# ProyectoFinal.net
KiCad netlist of a schematic drawn in EAGLE
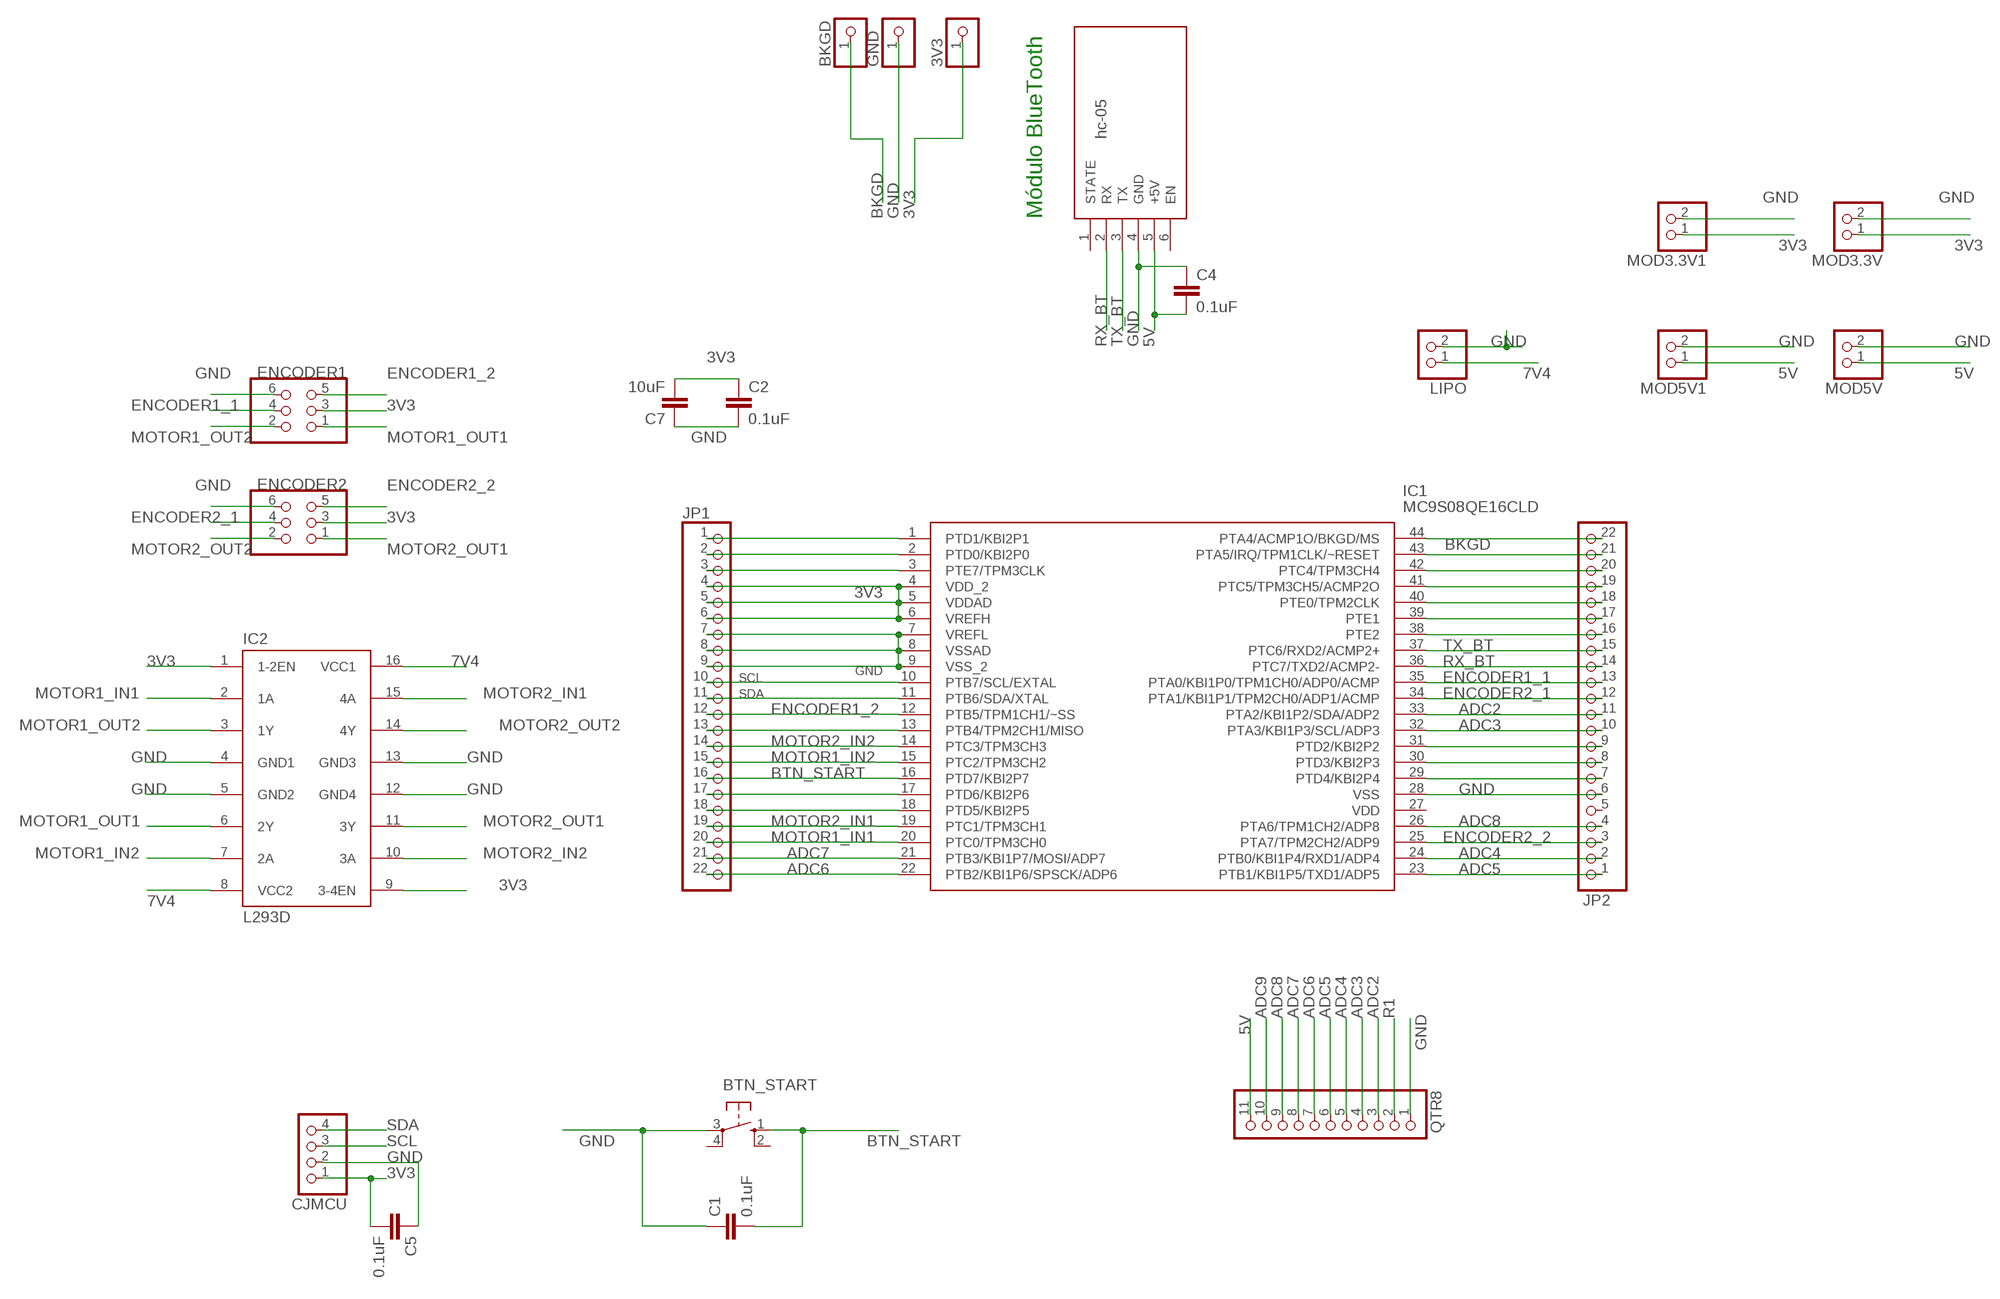
[diagram p0: schematic, sheet 1]

(export (version "E")
  (design (tool "Eeschema 10.0.6"))
  (components
    (comp (ref "3V3")
      (value "PINHD-1X1")
      (footprint "eagle-import:1X01")
      (libsource (lib "eagle-import") (part "PINHD-1X1"))
    )
    (comp (ref "BKGD")
      (value "PINHD-1X1")
      (footprint "eagle-import:1X01")
      (libsource (lib "eagle-import") (part "PINHD-1X1"))
    )
    (comp (ref "BLUETOOTH")
      (value "hc-05")
      (footprint "eagle-import:WIRELESS-BLUETOOTH-HC-05")
      (libsource (lib "eagle-import") (part "WIRELESS-BLUETOOTH-HC-05"))
    )
    (comp (ref "BTN_START")
      (value "10-XX")
      (footprint "eagle-import:B3F-10XX")
      (fields (field (name "MPN") "B3F-1000"))
      (libsource (lib "eagle-import") (part "10-XX"))
    )
    (comp (ref "C1")
      (value "0.1uF")
      (footprint "eagle-import:C0805K")
      (libsource (lib "eagle-import") (part "C-EUC0805K"))
    )
    (comp (ref "C2")
      (value "0.1uF")
      (footprint "eagle-import:C0805K")
      (libsource (lib "eagle-import") (part "C-EUC0805K"))
    )
    (comp (ref "C4")
      (value "0.1uF")
      (footprint "eagle-import:C0805K")
      (libsource (lib "eagle-import") (part "C-EUC0805K"))
    )
    (comp (ref "C5")
      (value "0.1uF")
      (footprint "eagle-import:C0805K")
      (libsource (lib "eagle-import") (part "C-EUC0805K"))
    )
    (comp (ref "C7")
      (value "10uF")
      (footprint "eagle-import:C1206K")
      (libsource (lib "eagle-import") (part "C-EUC1206K"))
    )
    (comp (ref "CJMCU")
      (value "PINHD-1X4")
      (footprint "eagle-import:1X04")
      (libsource (lib "eagle-import") (part "PINHD-1X4"))
    )
    (comp (ref "ENCODER1")
      (value "PINHD-2X3")
      (footprint "eagle-import:2X03")
      (libsource (lib "eagle-import") (part "PINHD-2X3"))
    )
    (comp (ref "ENCODER2")
      (value "PINHD-2X3")
      (footprint "eagle-import:2X03")
      (libsource (lib "eagle-import") (part "PINHD-2X3"))
    )
    (comp (ref "GND")
      (value "PINHD-1X1")
      (footprint "eagle-import:1X01")
      (libsource (lib "eagle-import") (part "PINHD-1X1"))
    )
    (comp (ref "IC1")
      (value "MC9S08QE16CLD")
      (footprint "eagle-import:QFP80P1200X1200X160-44N")
      (fields (field (name "MOUSER_PART_NUMBER") "841-MC9S08QE16CLD"))
      (libsource (lib "eagle-import") (part "MC9S08QE16CLD"))
    )
    (comp (ref "IC2")
      (value "L293D")
      (footprint "eagle-import:DIL16")
      (libsource (lib "eagle-import") (part "L293D"))
    )
    (comp (ref "JP1")
      (value "PINHD-1X22")
      (footprint "eagle-import:1X22")
      (libsource (lib "eagle-import") (part "PINHD-1X22"))
    )
    (comp (ref "JP2")
      (value "PINHD-1X22")
      (footprint "eagle-import:1X22")
      (libsource (lib "eagle-import") (part "PINHD-1X22"))
    )
    (comp (ref "LIPO")
      (value "PINHD-1X2")
      (footprint "eagle-import:1X02")
      (libsource (lib "eagle-import") (part "PINHD-1X2"))
    )
    (comp (ref "MOD3.3V")
      (value "PINHD-1X2")
      (footprint "eagle-import:1X02")
      (libsource (lib "eagle-import") (part "PINHD-1X2"))
    )
    (comp (ref "MOD3.3V1")
      (value "PINHD-1X2")
      (footprint "eagle-import:1X02")
      (libsource (lib "eagle-import") (part "PINHD-1X2"))
    )
    (comp (ref "MOD5V")
      (value "PINHD-1X2")
      (footprint "eagle-import:1X02")
      (libsource (lib "eagle-import") (part "PINHD-1X2"))
    )
    (comp (ref "MOD5V1")
      (value "PINHD-1X2")
      (footprint "eagle-import:1X02")
      (libsource (lib "eagle-import") (part "PINHD-1X2"))
    )
    (comp (ref "QTR8")
      (value "PINHD-1X11")
      (footprint "eagle-import:1X11")
      (libsource (lib "eagle-import") (part "PINHD-1X11"))
    )
  )
  (nets
    (net (code "1") (name "/3V3") (class "Default")
      (node (ref "3V3") (pin "1") (pinfunction "1_1") (pintype "passive"))
      (node (ref "C2") (pin "1") (pinfunction "1_1") (pintype "passive"))
      (node (ref "C5") (pin "2") (pinfunction "2_2") (pintype "passive"))
      (node (ref "C7") (pin "2") (pinfunction "2_2") (pintype "passive"))
      (node (ref "CJMCU") (pin "1") (pinfunction "1_1") (pintype "passive"))
      (node (ref "ENCODER1") (pin "3") (pinfunction "3_3") (pintype "passive"))
      (node (ref "ENCODER2") (pin "3") (pinfunction "3_3") (pintype "passive"))
      (node (ref "IC1") (pin "4") (pinfunction "VDD_2_4") (pintype "bidirectional"))
      (node (ref "IC1") (pin "5") (pinfunction "VDDAD_5") (pintype "bidirectional"))
      (node (ref "IC1") (pin "6") (pinfunction "VREFH_6") (pintype "bidirectional"))
      (node (ref "IC2") (pin "1") (pinfunction "1-2EN_1") (pintype "input"))
      (node (ref "IC2") (pin "9") (pinfunction "3-4EN_9") (pintype "input"))
      (node (ref "JP1") (pin "4") (pinfunction "4_4") (pintype "passive"))
      (node (ref "JP1") (pin "5") (pinfunction "5_5") (pintype "passive"))
      (node (ref "JP1") (pin "6") (pinfunction "6_6") (pintype "passive"))
      (node (ref "MOD3.3V") (pin "1") (pinfunction "1_1") (pintype "passive"))
      (node (ref "MOD3.3V1") (pin "1") (pinfunction "1_1") (pintype "passive"))
    )
    (net (code "2") (name "/5V") (class "Default")
      (node (ref "BLUETOOTH") (pin "5") (pinfunction "+5V_5") (pintype "power_in"))
      (node (ref "C4") (pin "2") (pinfunction "2_2") (pintype "passive"))
      (node (ref "MOD5V") (pin "1") (pinfunction "1_1") (pintype "passive"))
      (node (ref "MOD5V1") (pin "1") (pinfunction "1_1") (pintype "passive"))
      (node (ref "QTR8") (pin "11") (pinfunction "11_11") (pintype "passive"))
    )
    (net (code "3") (name "/7V4") (class "Default")
      (node (ref "IC2") (pin "16") (pinfunction "VCC1_16") (pintype "power_in"))
      (node (ref "IC2") (pin "8") (pinfunction "VCC2_8") (pintype "power_in"))
      (node (ref "LIPO") (pin "1") (pinfunction "1_1") (pintype "passive"))
    )
    (net (code "4") (name "/ADC2") (class "Default")
      (node (ref "IC1") (pin "33") (pinfunction "PTA2/KBI1P2/SDA/ADP2_33") (pintype "bidirectional"))
      (node (ref "JP2") (pin "11") (pinfunction "11_11") (pintype "passive"))
      (node (ref "QTR8") (pin "3") (pinfunction "3_3") (pintype "passive"))
    )
    (net (code "5") (name "/ADC3") (class "Default")
      (node (ref "IC1") (pin "32") (pinfunction "PTA3/KBI1P3/SCL/ADP3_32") (pintype "bidirectional"))
      (node (ref "JP2") (pin "10") (pinfunction "10_10") (pintype "passive"))
      (node (ref "QTR8") (pin "4") (pinfunction "4_4") (pintype "passive"))
    )
    (net (code "6") (name "/ADC4") (class "Default")
      (node (ref "IC1") (pin "24") (pinfunction "PTB0/KBI1P4/RXD1/ADP4_24") (pintype "bidirectional"))
      (node (ref "JP2") (pin "2") (pinfunction "2_2") (pintype "passive"))
      (node (ref "QTR8") (pin "5") (pinfunction "5_5") (pintype "passive"))
    )
    (net (code "7") (name "/ADC5") (class "Default")
      (node (ref "IC1") (pin "23") (pinfunction "PTB1/KBI1P5/TXD1/ADP5_23") (pintype "bidirectional"))
      (node (ref "JP2") (pin "1") (pinfunction "1_1") (pintype "passive"))
      (node (ref "QTR8") (pin "6") (pinfunction "6_6") (pintype "passive"))
    )
    (net (code "8") (name "/ADC6") (class "Default")
      (node (ref "IC1") (pin "22") (pinfunction "PTB2/KBI1P6/SPSCK/ADP6_22") (pintype "bidirectional"))
      (node (ref "JP1") (pin "22") (pinfunction "22_22") (pintype "passive"))
      (node (ref "QTR8") (pin "7") (pinfunction "7_7") (pintype "passive"))
    )
    (net (code "9") (name "/ADC7") (class "Default")
      (node (ref "IC1") (pin "21") (pinfunction "PTB3/KBI1P7/MOSI/ADP7_21") (pintype "bidirectional"))
      (node (ref "JP1") (pin "21") (pinfunction "21_21") (pintype "passive"))
      (node (ref "QTR8") (pin "8") (pinfunction "8_8") (pintype "passive"))
    )
    (net (code "10") (name "/ADC8") (class "Default")
      (node (ref "IC1") (pin "26") (pinfunction "PTA6/TPM1CH2/ADP8_26") (pintype "bidirectional"))
      (node (ref "JP2") (pin "4") (pinfunction "4_4") (pintype "passive"))
      (node (ref "QTR8") (pin "9") (pinfunction "9_9") (pintype "passive"))
    )
    (net (code "11") (name "/ADC9") (class "Default")
      (node (ref "QTR8") (pin "10") (pinfunction "10_10") (pintype "passive"))
    )
    (net (code "12") (name "/BKGD") (class "Default")
      (node (ref "BKGD") (pin "1") (pinfunction "1_1") (pintype "passive"))
      (node (ref "IC1") (pin "44") (pinfunction "PTA4/ACMP1O/BKGD/MS_44") (pintype "bidirectional"))
      (node (ref "JP2") (pin "22") (pinfunction "22_22") (pintype "passive"))
    )
    (net (code "13") (name "/BTN_START") (class "Default")
      (node (ref "BTN_START") (pin "1") (pinfunction "S_1") (pintype "passive"))
      (node (ref "C1") (pin "2") (pinfunction "2_2") (pintype "passive"))
      (node (ref "IC1") (pin "16") (pinfunction "PTD7/KBI2P7_16") (pintype "bidirectional"))
      (node (ref "JP1") (pin "16") (pinfunction "16_16") (pintype "passive"))
    )
    (net (code "14") (name "/ENCODER1_1") (class "Default")
      (node (ref "ENCODER1") (pin "4") (pinfunction "4_4") (pintype "passive"))
      (node (ref "IC1") (pin "35") (pinfunction "PTA0/KBI1P0/TPM1CH0/ADP0/ACMP_35") (pintype "bidirectional"))
      (node (ref "JP2") (pin "13") (pinfunction "13_13") (pintype "passive"))
    )
    (net (code "15") (name "/ENCODER1_2") (class "Default")
      (node (ref "ENCODER1") (pin "5") (pinfunction "5_5") (pintype "passive"))
      (node (ref "IC1") (pin "12") (pinfunction "PTB5/TPM1CH1/~{SS}_12") (pintype "bidirectional"))
      (node (ref "JP1") (pin "12") (pinfunction "12_12") (pintype "passive"))
    )
    (net (code "16") (name "/ENCODER2_1") (class "Default")
      (node (ref "ENCODER2") (pin "4") (pinfunction "4_4") (pintype "passive"))
      (node (ref "IC1") (pin "34") (pinfunction "PTA1/KBI1P1/TPM2CH0/ADP1/ACMP_34") (pintype "bidirectional"))
      (node (ref "JP2") (pin "12") (pinfunction "12_12") (pintype "passive"))
    )
    (net (code "17") (name "/ENCODER2_2") (class "Default")
      (node (ref "ENCODER2") (pin "5") (pinfunction "5_5") (pintype "passive"))
      (node (ref "IC1") (pin "25") (pinfunction "PTA7/TPM2CH2/ADP9_25") (pintype "bidirectional"))
      (node (ref "JP2") (pin "3") (pinfunction "3_3") (pintype "passive"))
    )
    (net (code "18") (name "/GND") (class "Default")
      (node (ref "BLUETOOTH") (pin "4") (pinfunction "GND_4") (pintype "power_in"))
      (node (ref "BTN_START") (pin "3") (pinfunction "P_3") (pintype "passive"))
      (node (ref "C1") (pin "1") (pinfunction "1_1") (pintype "passive"))
      (node (ref "C2") (pin "2") (pinfunction "2_2") (pintype "passive"))
      (node (ref "C4") (pin "1") (pinfunction "1_1") (pintype "passive"))
      (node (ref "C5") (pin "1") (pinfunction "1_1") (pintype "passive"))
      (node (ref "C7") (pin "1") (pinfunction "1_1") (pintype "passive"))
      (node (ref "CJMCU") (pin "2") (pinfunction "2_2") (pintype "passive"))
      (node (ref "ENCODER1") (pin "6") (pinfunction "6_6") (pintype "passive"))
      (node (ref "ENCODER2") (pin "6") (pinfunction "6_6") (pintype "passive"))
      (node (ref "GND") (pin "1") (pinfunction "1_1") (pintype "passive"))
      (node (ref "IC1") (pin "28") (pinfunction "VSS_28") (pintype "bidirectional"))
      (node (ref "IC1") (pin "7") (pinfunction "VREFL_7") (pintype "bidirectional"))
      (node (ref "IC1") (pin "8") (pinfunction "VSSAD_8") (pintype "bidirectional"))
      (node (ref "IC1") (pin "9") (pinfunction "VSS_2_9") (pintype "bidirectional"))
      (node (ref "IC2") (pin "12") (pinfunction "GND4_12") (pintype "power_in"))
      (node (ref "IC2") (pin "13") (pinfunction "GND3_13") (pintype "power_in"))
      (node (ref "IC2") (pin "4") (pinfunction "GND1_4") (pintype "power_in"))
      (node (ref "IC2") (pin "5") (pinfunction "GND2_5") (pintype "power_in"))
      (node (ref "JP1") (pin "7") (pinfunction "7_7") (pintype "passive"))
      (node (ref "JP1") (pin "8") (pinfunction "8_8") (pintype "passive"))
      (node (ref "JP1") (pin "9") (pinfunction "9_9") (pintype "passive"))
      (node (ref "JP2") (pin "6") (pinfunction "6_6") (pintype "passive"))
      (node (ref "LIPO") (pin "2") (pinfunction "2_2") (pintype "passive"))
      (node (ref "MOD3.3V") (pin "2") (pinfunction "2_2") (pintype "passive"))
      (node (ref "MOD3.3V1") (pin "2") (pinfunction "2_2") (pintype "passive"))
      (node (ref "MOD5V") (pin "2") (pinfunction "2_2") (pintype "passive"))
      (node (ref "MOD5V1") (pin "2") (pinfunction "2_2") (pintype "passive"))
      (node (ref "QTR8") (pin "1") (pinfunction "1_1") (pintype "passive"))
    )
    (net (code "19") (name "/MOTOR1_IN1") (class "Default")
      (node (ref "IC1") (pin "20") (pinfunction "PTC0/TPM3CH0_20") (pintype "bidirectional"))
      (node (ref "IC2") (pin "2") (pinfunction "1A_2") (pintype "input"))
      (node (ref "JP1") (pin "20") (pinfunction "20_20") (pintype "passive"))
    )
    (net (code "20") (name "/MOTOR1_IN2") (class "Default")
      (node (ref "IC1") (pin "15") (pinfunction "PTC2/TPM3CH2_15") (pintype "bidirectional"))
      (node (ref "IC2") (pin "7") (pinfunction "2A_7") (pintype "input"))
      (node (ref "JP1") (pin "15") (pinfunction "15_15") (pintype "passive"))
    )
    (net (code "21") (name "/MOTOR1_OUT1") (class "Default")
      (node (ref "ENCODER1") (pin "1") (pinfunction "1_1") (pintype "passive"))
      (node (ref "IC2") (pin "6") (pinfunction "2Y_6") (pintype "output"))
    )
    (net (code "22") (name "/MOTOR1_OUT2") (class "Default")
      (node (ref "ENCODER1") (pin "2") (pinfunction "2_2") (pintype "passive"))
      (node (ref "IC2") (pin "3") (pinfunction "1Y_3") (pintype "output"))
    )
    (net (code "23") (name "/MOTOR2_IN1") (class "Default")
      (node (ref "IC1") (pin "19") (pinfunction "PTC1/TPM3CH1_19") (pintype "bidirectional"))
      (node (ref "IC2") (pin "15") (pinfunction "4A_15") (pintype "input"))
      (node (ref "JP1") (pin "19") (pinfunction "19_19") (pintype "passive"))
    )
    (net (code "24") (name "/MOTOR2_IN2") (class "Default")
      (node (ref "IC1") (pin "14") (pinfunction "PTC3/TPM3CH3_14") (pintype "bidirectional"))
      (node (ref "IC2") (pin "10") (pinfunction "3A_10") (pintype "input"))
      (node (ref "JP1") (pin "14") (pinfunction "14_14") (pintype "passive"))
    )
    (net (code "25") (name "/MOTOR2_OUT1") (class "Default")
      (node (ref "ENCODER2") (pin "1") (pinfunction "1_1") (pintype "passive"))
      (node (ref "IC2") (pin "11") (pinfunction "3Y_11") (pintype "output"))
    )
    (net (code "26") (name "/MOTOR2_OUT2") (class "Default")
      (node (ref "ENCODER2") (pin "2") (pinfunction "2_2") (pintype "passive"))
      (node (ref "IC2") (pin "14") (pinfunction "4Y_14") (pintype "output"))
    )
    (net (code "27") (name "/R1") (class "Default")
      (node (ref "QTR8") (pin "2") (pinfunction "2_2") (pintype "passive"))
    )
    (net (code "28") (name "/RX_BT") (class "Default")
      (node (ref "BLUETOOTH") (pin "2") (pinfunction "RX_2") (pintype "bidirectional"))
      (node (ref "IC1") (pin "36") (pinfunction "PTC7/TXD2/ACMP2-_36") (pintype "bidirectional"))
      (node (ref "JP2") (pin "14") (pinfunction "14_14") (pintype "passive"))
    )
    (net (code "29") (name "/SCL") (class "Default")
      (node (ref "CJMCU") (pin "3") (pinfunction "3_3") (pintype "passive"))
      (node (ref "IC1") (pin "10") (pinfunction "PTB7/SCL/EXTAL_10") (pintype "bidirectional"))
      (node (ref "JP1") (pin "10") (pinfunction "10_10") (pintype "passive"))
    )
    (net (code "30") (name "/SDA") (class "Default")
      (node (ref "CJMCU") (pin "4") (pinfunction "4_4") (pintype "passive"))
      (node (ref "IC1") (pin "11") (pinfunction "PTB6/SDA/XTAL_11") (pintype "bidirectional"))
      (node (ref "JP1") (pin "11") (pinfunction "11_11") (pintype "passive"))
    )
    (net (code "31") (name "/TX_BT") (class "Default")
      (node (ref "BLUETOOTH") (pin "3") (pinfunction "TX_3") (pintype "bidirectional"))
      (node (ref "IC1") (pin "37") (pinfunction "PTC6/RXD2/ACMP2+_37") (pintype "bidirectional"))
      (node (ref "JP2") (pin "15") (pinfunction "15_15") (pintype "passive"))
    )
    (net (code "32") (name "Net-(IC1-PTA5{slash}IRQ{slash}TPM1CLK{slash}~{RESET})") (class "Default")
      (node (ref "IC1") (pin "43") (pinfunction "PTA5/IRQ/TPM1CLK/~{RESET}_43") (pintype "bidirectional"))
      (node (ref "JP2") (pin "21") (pinfunction "21_21") (pintype "passive"))
    )
    (net (code "33") (name "Net-(IC1-PTB4{slash}TPM2CH1{slash}MISO)") (class "Default")
      (node (ref "IC1") (pin "13") (pinfunction "PTB4/TPM2CH1/MISO_13") (pintype "bidirectional"))
      (node (ref "JP1") (pin "13") (pinfunction "13_13") (pintype "passive"))
    )
    (net (code "34") (name "Net-(IC1-PTC4{slash}TPM3CH4)") (class "Default")
      (node (ref "IC1") (pin "42") (pinfunction "PTC4/TPM3CH4_42") (pintype "bidirectional"))
      (node (ref "JP2") (pin "20") (pinfunction "20_20") (pintype "passive"))
    )
    (net (code "35") (name "Net-(IC1-PTC5{slash}TPM3CH5{slash}ACMP2O)") (class "Default")
      (node (ref "IC1") (pin "41") (pinfunction "PTC5/TPM3CH5/ACMP2O_41") (pintype "bidirectional"))
      (node (ref "JP2") (pin "19") (pinfunction "19_19") (pintype "passive"))
    )
    (net (code "36") (name "Net-(IC1-PTD0{slash}KBI2P0)") (class "Default")
      (node (ref "IC1") (pin "2") (pinfunction "PTD0/KBI2P0_2") (pintype "bidirectional"))
      (node (ref "JP1") (pin "2") (pinfunction "2_2") (pintype "passive"))
    )
    (net (code "37") (name "Net-(IC1-PTD1{slash}KBI2P1)") (class "Default")
      (node (ref "IC1") (pin "1") (pinfunction "PTD1/KBI2P1_1") (pintype "bidirectional"))
      (node (ref "JP1") (pin "1") (pinfunction "1_1") (pintype "passive"))
    )
    (net (code "38") (name "Net-(IC1-PTD2{slash}KBI2P2)") (class "Default")
      (node (ref "IC1") (pin "31") (pinfunction "PTD2/KBI2P2_31") (pintype "bidirectional"))
      (node (ref "JP2") (pin "9") (pinfunction "9_9") (pintype "passive"))
    )
    (net (code "39") (name "Net-(IC1-PTD3{slash}KBI2P3)") (class "Default")
      (node (ref "IC1") (pin "30") (pinfunction "PTD3/KBI2P3_30") (pintype "bidirectional"))
      (node (ref "JP2") (pin "8") (pinfunction "8_8") (pintype "passive"))
    )
    (net (code "40") (name "Net-(IC1-PTD4{slash}KBI2P4)") (class "Default")
      (node (ref "IC1") (pin "29") (pinfunction "PTD4/KBI2P4_29") (pintype "bidirectional"))
      (node (ref "JP2") (pin "7") (pinfunction "7_7") (pintype "passive"))
    )
    (net (code "41") (name "Net-(IC1-PTD5{slash}KBI2P5)") (class "Default")
      (node (ref "IC1") (pin "18") (pinfunction "PTD5/KBI2P5_18") (pintype "bidirectional"))
      (node (ref "JP1") (pin "18") (pinfunction "18_18") (pintype "passive"))
    )
    (net (code "42") (name "Net-(IC1-PTD6{slash}KBI2P6)") (class "Default")
      (node (ref "IC1") (pin "17") (pinfunction "PTD6/KBI2P6_17") (pintype "bidirectional"))
      (node (ref "JP1") (pin "17") (pinfunction "17_17") (pintype "passive"))
    )
    (net (code "43") (name "Net-(IC1-PTE0{slash}TPM2CLK)") (class "Default")
      (node (ref "IC1") (pin "40") (pinfunction "PTE0/TPM2CLK_40") (pintype "bidirectional"))
      (node (ref "JP2") (pin "18") (pinfunction "18_18") (pintype "passive"))
    )
    (net (code "44") (name "Net-(IC1-PTE1)") (class "Default")
      (node (ref "IC1") (pin "39") (pinfunction "PTE1_39") (pintype "bidirectional"))
      (node (ref "JP2") (pin "17") (pinfunction "17_17") (pintype "passive"))
    )
    (net (code "45") (name "Net-(IC1-PTE2)") (class "Default")
      (node (ref "IC1") (pin "38") (pinfunction "PTE2_38") (pintype "bidirectional"))
      (node (ref "JP2") (pin "16") (pinfunction "16_16") (pintype "passive"))
    )
    (net (code "46") (name "Net-(IC1-PTE7{slash}TPM3CLK)") (class "Default")
      (node (ref "IC1") (pin "3") (pinfunction "PTE7/TPM3CLK_3") (pintype "bidirectional"))
      (node (ref "JP1") (pin "3") (pinfunction "3_3") (pintype "passive"))
    )
    (net (code "47") (name "unconnected-(BLUETOOTH-EN-Pad6)") (class "Default")
      (node (ref "BLUETOOTH") (pin "6") (pinfunction "EN_6") (pintype "bidirectional"))
    )
    (net (code "48") (name "unconnected-(BLUETOOTH-STATE-Pad1)") (class "Default")
      (node (ref "BLUETOOTH") (pin "1") (pinfunction "STATE_1") (pintype "bidirectional"))
    )
    (net (code "49") (name "unconnected-(BTN_START-P1-Pad4)") (class "Default")
      (node (ref "BTN_START") (pin "4") (pinfunction "P1_4") (pintype "passive"))
    )
    (net (code "50") (name "unconnected-(BTN_START-S1-Pad2)") (class "Default")
      (node (ref "BTN_START") (pin "2") (pinfunction "S1_2") (pintype "passive"))
    )
    (net (code "51") (name "unconnected-(IC1-VDD-Pad27)") (class "Default")
      (node (ref "IC1") (pin "27") (pinfunction "VDD_27") (pintype "bidirectional"))
    )
    (net (code "52") (name "unconnected-(JP2-Pad5)") (class "Default")
      (node (ref "JP2") (pin "5") (pinfunction "5_5") (pintype "passive"))
    )
  )
)
